# schematic.net
KiCad netlist of a schematic drawn in EasyEDA
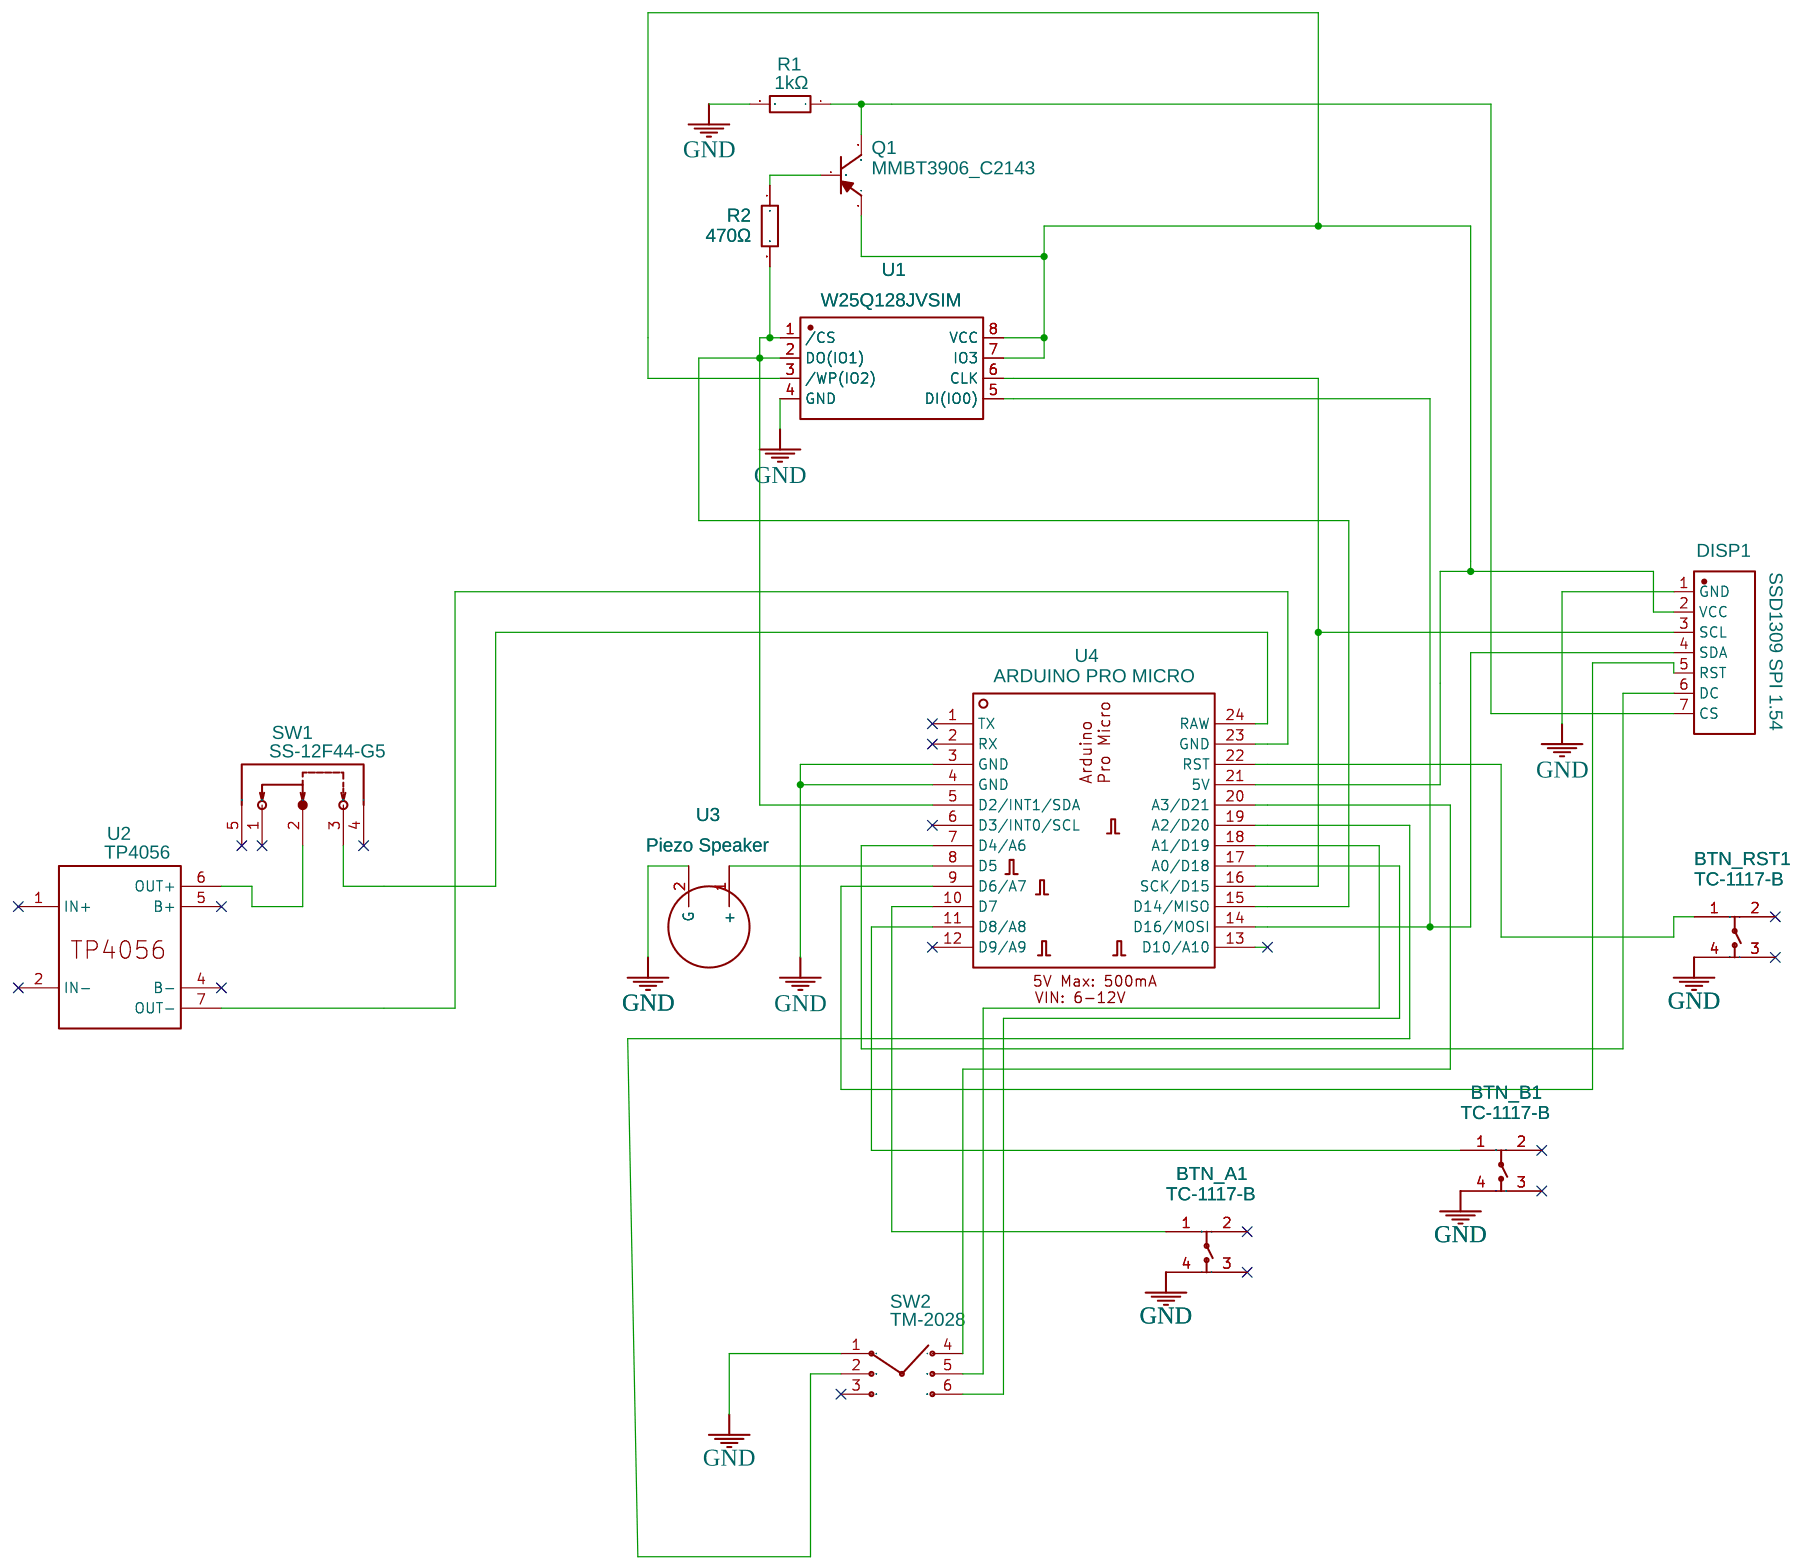
[diagram p0: schematic sheet]

(export (version "E")
  (design (tool "Eeschema 10.0.6"))
  (components
    (comp (ref "BTN_A1")
      (value "TC-1117-B")
      (fields (field (name "Manufacturer") "XKB Connectivity(中国星坤)"))
      (libsource (lib "") (part "TC-1117-B_2"))
    )
    (comp (ref "BTN_B1")
      (value "TC-1117-B")
      (fields (field (name "Manufacturer") "XKB Connectivity(中国星坤)"))
      (libsource (lib "") (part "TC-1117-B_1"))
    )
    (comp (ref "BTN_RST1")
      (value "TC-1117-B")
      (fields (field (name "Manufacturer") "XKB Connectivity(中国星坤)"))
      (libsource (lib "") (part "TC-1117-B"))
    )
    (comp (ref "DISP1") (value "SSD1309 SPI 1.54") (libsource (lib "") (part "SSD1309 SPI 1.54")))
    (comp (ref "Q1")
      (value "MMBT3906_C2143")
      (fields (field (name "Manufacturer Part") "MMBT3906 2A") (field (name "Manufacturer") "CJ(江苏长电/长晶)"))
      (libsource (lib "") (part "MMBT3906_C2143"))
    )
    (comp (ref "R1")
      (value "1kΩ")
      (fields (field (name "Manufacturer Part") "RC0805FR-071KL") (field (name "Manufacturer") "YAGEO(国巨)"))
      (libsource (lib "") (part "RC0805FR-071KL"))
    )
    (comp (ref "R2")
      (value "470Ω")
      (fields (field (name "Manufacturer Part") "RC0805FR-07470RL") (field (name "Manufacturer") "YAGEO(国巨)"))
      (libsource (lib "") (part "RC0805FR-07470RL"))
    )
    (comp (ref "SW1")
      (value "SS-12F44-G5")
      (fields (field (name "Manufacturer") "韩国韩荣"))
      (libsource (lib "") (part "SS-12F44-G5"))
    )
    (comp (ref "SW2")
      (value "TM-2028")
      (fields (field (name "Manufacturer") "XKB Connection(中国星坤)"))
      (libsource (lib "") (part "TM-2028"))
    )
    (comp (ref "U1")
      (value "W25Q128JVSIM")
      (fields (field (name "Manufacturer") "WINBOND(华邦)"))
      (libsource (lib "") (part "W25Q128JVSIM"))
    )
    (comp (ref "U2")
      (value "TP4056")
      (fields (field (name "Manufacturer Part") "1198156") (field (name "Manufacturer") "Banggood"))
      (libsource (lib "") (part "TP4056 COPY"))
    )
    (comp (ref "U3") (value "Piezo Speaker") (libsource (lib "") (part "Piezo Speaker")))
    (comp (ref "U4") (value "ARDUINO PRO MICRO") (libsource (lib "") (part "ARDUINO PRO MICRO")))
  )
  (nets
    (net (code "1") (name "GND") (class "Default")
      (node (ref "BTN_A1") (pin "4") (pinfunction "4_4") (pintype "unspecified"))
      (node (ref "BTN_B1") (pin "4") (pinfunction "4_4") (pintype "unspecified"))
      (node (ref "BTN_RST1") (pin "4") (pinfunction "4_4") (pintype "unspecified"))
      (node (ref "DISP1") (pin "1") (pinfunction "GND_1") (pintype "unspecified"))
      (node (ref "R1") (pin "2") (pinfunction "2_2") (pintype "input"))
      (node (ref "SW2") (pin "1") (pinfunction "1_1") (pintype "unspecified"))
      (node (ref "U1") (pin "4") (pinfunction "GND_4") (pintype "unspecified"))
      (node (ref "U3") (pin "2") (pinfunction "G_2") (pintype "unspecified"))
      (node (ref "U4") (pin "3") (pinfunction "GND_3") (pintype "unspecified"))
      (node (ref "U4") (pin "4") (pinfunction "GND_4") (pintype "unspecified"))
    )
    (net (code "2") (name "Net-(DISP1-CS)") (class "Default")
      (node (ref "DISP1") (pin "7") (pinfunction "CS_7") (pintype "unspecified"))
      (node (ref "Q1") (pin "3") (pinfunction "C_3") (pintype "unspecified"))
      (node (ref "R1") (pin "1") (pinfunction "1_1") (pintype "input"))
    )
    (net (code "3") (name "Net-(DISP1-DC)") (class "Default")
      (node (ref "DISP1") (pin "6") (pinfunction "DC_6") (pintype "unspecified"))
      (node (ref "U4") (pin "7") (pinfunction "D4/A6_7") (pintype "unspecified"))
    )
    (net (code "4") (name "Net-(DISP1-RST)") (class "Default")
      (node (ref "DISP1") (pin "5") (pinfunction "RST_5") (pintype "unspecified"))
      (node (ref "U4") (pin "9") (pinfunction "D6/A7_9") (pintype "unspecified"))
    )
    (net (code "5") (name "Net-(DISP1-SCL)") (class "Default")
      (node (ref "DISP1") (pin "3") (pinfunction "SCL_3") (pintype "unspecified"))
      (node (ref "U1") (pin "6") (pinfunction "CLK_6") (pintype "unspecified"))
      (node (ref "U4") (pin "16") (pinfunction "SCK/D15_16") (pintype "unspecified"))
    )
    (net (code "6") (name "Net-(DISP1-SDA)") (class "Default")
      (node (ref "DISP1") (pin "4") (pinfunction "SDA_4") (pintype "unspecified"))
      (node (ref "U1") (pin "5") (pinfunction "DI(IO0)_5") (pintype "unspecified"))
      (node (ref "U4") (pin "14") (pinfunction "D16/MOSI_14") (pintype "unspecified"))
    )
    (net (code "7") (name "Net-(DISP1-VCC)") (class "Default")
      (node (ref "DISP1") (pin "2") (pinfunction "VCC_2") (pintype "unspecified"))
      (node (ref "Q1") (pin "2") (pinfunction "E_2") (pintype "unspecified"))
      (node (ref "U1") (pin "3") (pinfunction "/WP(IO2)_3") (pintype "unspecified"))
      (node (ref "U1") (pin "7") (pinfunction "IO3_7") (pintype "unspecified"))
      (node (ref "U1") (pin "8") (pinfunction "VCC_8") (pintype "unspecified"))
      (node (ref "U4") (pin "21") (pinfunction "5V_21") (pintype "unspecified"))
    )
    (net (code "8") (name "Net-(Q1-B)") (class "Default")
      (node (ref "Q1") (pin "1") (pinfunction "B_1") (pintype "unspecified"))
      (node (ref "R2") (pin "1") (pinfunction "1_1") (pintype "input"))
    )
    (net (code "9") (name "Net-(U1-DO(IO1))") (class "Default")
      (node (ref "R2") (pin "2") (pinfunction "2_2") (pintype "input"))
      (node (ref "U1") (pin "1") (pinfunction "/CS_1") (pintype "unspecified"))
      (node (ref "U1") (pin "2") (pinfunction "DO(IO1)_2") (pintype "unspecified"))
      (node (ref "U4") (pin "15") (pinfunction "D14/MISO_15") (pintype "unspecified"))
      (node (ref "U4") (pin "5") (pinfunction "D2/INT1/SDA_5") (pintype "unspecified"))
    )
    (net (code "10") (name "Net-(U2-OUT+)") (class "Default")
      (node (ref "SW1") (pin "2") (pinfunction "2_2") (pintype "unspecified"))
      (node (ref "U2") (pin "6") (pinfunction "OUT+_6") (pintype "unspecified"))
    )
    (net (code "11") (name "Net-(U2-OUT-)") (class "Default")
      (node (ref "U2") (pin "7") (pinfunction "OUT-_7") (pintype "unspecified"))
      (node (ref "U4") (pin "23") (pinfunction "GND_23") (pintype "unspecified"))
    )
    (net (code "12") (name "Net-(U3-+)") (class "Default")
      (node (ref "U3") (pin "1") (pinfunction "+_1") (pintype "unspecified"))
      (node (ref "U4") (pin "8") (pinfunction "D5_8") (pintype "unspecified"))
    )
    (net (code "13") (name "Net-(U4-A0{slash}D18)") (class "Default")
      (node (ref "SW2") (pin "6") (pinfunction "6_6") (pintype "unspecified"))
      (node (ref "U4") (pin "17") (pinfunction "A0/D18_17") (pintype "unspecified"))
    )
    (net (code "14") (name "Net-(U4-A1{slash}D19)") (class "Default")
      (node (ref "SW2") (pin "5") (pinfunction "5_5") (pintype "unspecified"))
      (node (ref "U4") (pin "18") (pinfunction "A1/D19_18") (pintype "unspecified"))
    )
    (net (code "15") (name "Net-(U4-A2{slash}D20)") (class "Default")
      (node (ref "SW2") (pin "2") (pinfunction "2_2") (pintype "unspecified"))
      (node (ref "U4") (pin "19") (pinfunction "A2/D20_19") (pintype "unspecified"))
    )
    (net (code "16") (name "Net-(U4-A3{slash}D21)") (class "Default")
      (node (ref "SW2") (pin "4") (pinfunction "4_4") (pintype "unspecified"))
      (node (ref "U4") (pin "20") (pinfunction "A3/D21_20") (pintype "unspecified"))
    )
    (net (code "17") (name "Net-(U4-D7)") (class "Default")
      (node (ref "BTN_A1") (pin "1") (pinfunction "1_1") (pintype "unspecified"))
      (node (ref "U4") (pin "10") (pinfunction "D7_10") (pintype "unspecified"))
    )
    (net (code "18") (name "Net-(U4-D8{slash}A8)") (class "Default")
      (node (ref "BTN_B1") (pin "1") (pinfunction "1_1") (pintype "unspecified"))
      (node (ref "U4") (pin "11") (pinfunction "D8/A8_11") (pintype "unspecified"))
    )
    (net (code "19") (name "Net-(U4-RAW)") (class "Default")
      (node (ref "SW1") (pin "3") (pinfunction "3_3") (pintype "unspecified"))
      (node (ref "U4") (pin "24") (pinfunction "RAW_24") (pintype "unspecified"))
    )
    (net (code "20") (name "Net-(U4-RST)") (class "Default")
      (node (ref "BTN_RST1") (pin "1") (pinfunction "1_1") (pintype "unspecified"))
      (node (ref "U4") (pin "22") (pinfunction "RST_22") (pintype "unspecified"))
    )
    (net (code "21") (name "unconnected-(BTN_A1-Pad2)") (class "Default")
      (node (ref "BTN_A1") (pin "2") (pinfunction "2_2") (pintype "unspecified+no_connect"))
    )
    (net (code "22") (name "unconnected-(BTN_A1-Pad3)") (class "Default")
      (node (ref "BTN_A1") (pin "3") (pinfunction "3_3") (pintype "unspecified+no_connect"))
    )
    (net (code "23") (name "unconnected-(BTN_B1-Pad2)") (class "Default")
      (node (ref "BTN_B1") (pin "2") (pinfunction "2_2") (pintype "unspecified+no_connect"))
    )
    (net (code "24") (name "unconnected-(BTN_B1-Pad3)") (class "Default")
      (node (ref "BTN_B1") (pin "3") (pinfunction "3_3") (pintype "unspecified+no_connect"))
    )
    (net (code "25") (name "unconnected-(BTN_RST1-Pad2)") (class "Default")
      (node (ref "BTN_RST1") (pin "2") (pinfunction "2_2") (pintype "unspecified+no_connect"))
    )
    (net (code "26") (name "unconnected-(BTN_RST1-Pad3)") (class "Default")
      (node (ref "BTN_RST1") (pin "3") (pinfunction "3_3") (pintype "unspecified+no_connect"))
    )
    (net (code "27") (name "unconnected-(SW1-Pad1)") (class "Default")
      (node (ref "SW1") (pin "1") (pinfunction "1_1") (pintype "unspecified+no_connect"))
    )
    (net (code "28") (name "unconnected-(SW1-Pad4)") (class "Default")
      (node (ref "SW1") (pin "4") (pinfunction "4_4") (pintype "unspecified+no_connect"))
    )
    (net (code "29") (name "unconnected-(SW1-Pad5)") (class "Default")
      (node (ref "SW1") (pin "5") (pinfunction "5_5") (pintype "unspecified+no_connect"))
    )
    (net (code "30") (name "unconnected-(SW2-Pad3)") (class "Default")
      (node (ref "SW2") (pin "3") (pinfunction "3_3") (pintype "unspecified+no_connect"))
    )
    (net (code "31") (name "unconnected-(U2-B+-Pad5)") (class "Default")
      (node (ref "U2") (pin "5") (pinfunction "B+_5") (pintype "unspecified+no_connect"))
    )
    (net (code "32") (name "unconnected-(U2-B--Pad4)") (class "Default")
      (node (ref "U2") (pin "4") (pinfunction "B-_4") (pintype "unspecified+no_connect"))
    )
    (net (code "33") (name "unconnected-(U2-IN+-Pad1)") (class "Default")
      (node (ref "U2") (pin "1") (pinfunction "IN+_1") (pintype "unspecified+no_connect"))
    )
    (net (code "34") (name "unconnected-(U2-IN--Pad2)") (class "Default")
      (node (ref "U2") (pin "2") (pinfunction "IN-_2") (pintype "unspecified+no_connect"))
    )
    (net (code "35") (name "unconnected-(U4-D3{slash}INT0{slash}SCL-Pad6)") (class "Default")
      (node (ref "U4") (pin "6") (pinfunction "D3/INT0/SCL_6") (pintype "unspecified+no_connect"))
    )
    (net (code "36") (name "unconnected-(U4-D9{slash}A9-Pad12)") (class "Default")
      (node (ref "U4") (pin "12") (pinfunction "D9/A9_12") (pintype "unspecified+no_connect"))
    )
    (net (code "37") (name "unconnected-(U4-D10{slash}A10-Pad13)") (class "Default")
      (node (ref "U4") (pin "13") (pinfunction "D10/A10_13") (pintype "unspecified+no_connect"))
    )
    (net (code "38") (name "unconnected-(U4-RX-Pad2)") (class "Default")
      (node (ref "U4") (pin "2") (pinfunction "RX_2") (pintype "unspecified+no_connect"))
    )
    (net (code "39") (name "unconnected-(U4-TX-Pad1)") (class "Default")
      (node (ref "U4") (pin "1") (pinfunction "TX_1") (pintype "unspecified+no_connect"))
    )
  )
)
